# Volant5.net
KiCad netlist of a schematic drawn in Altium Designer
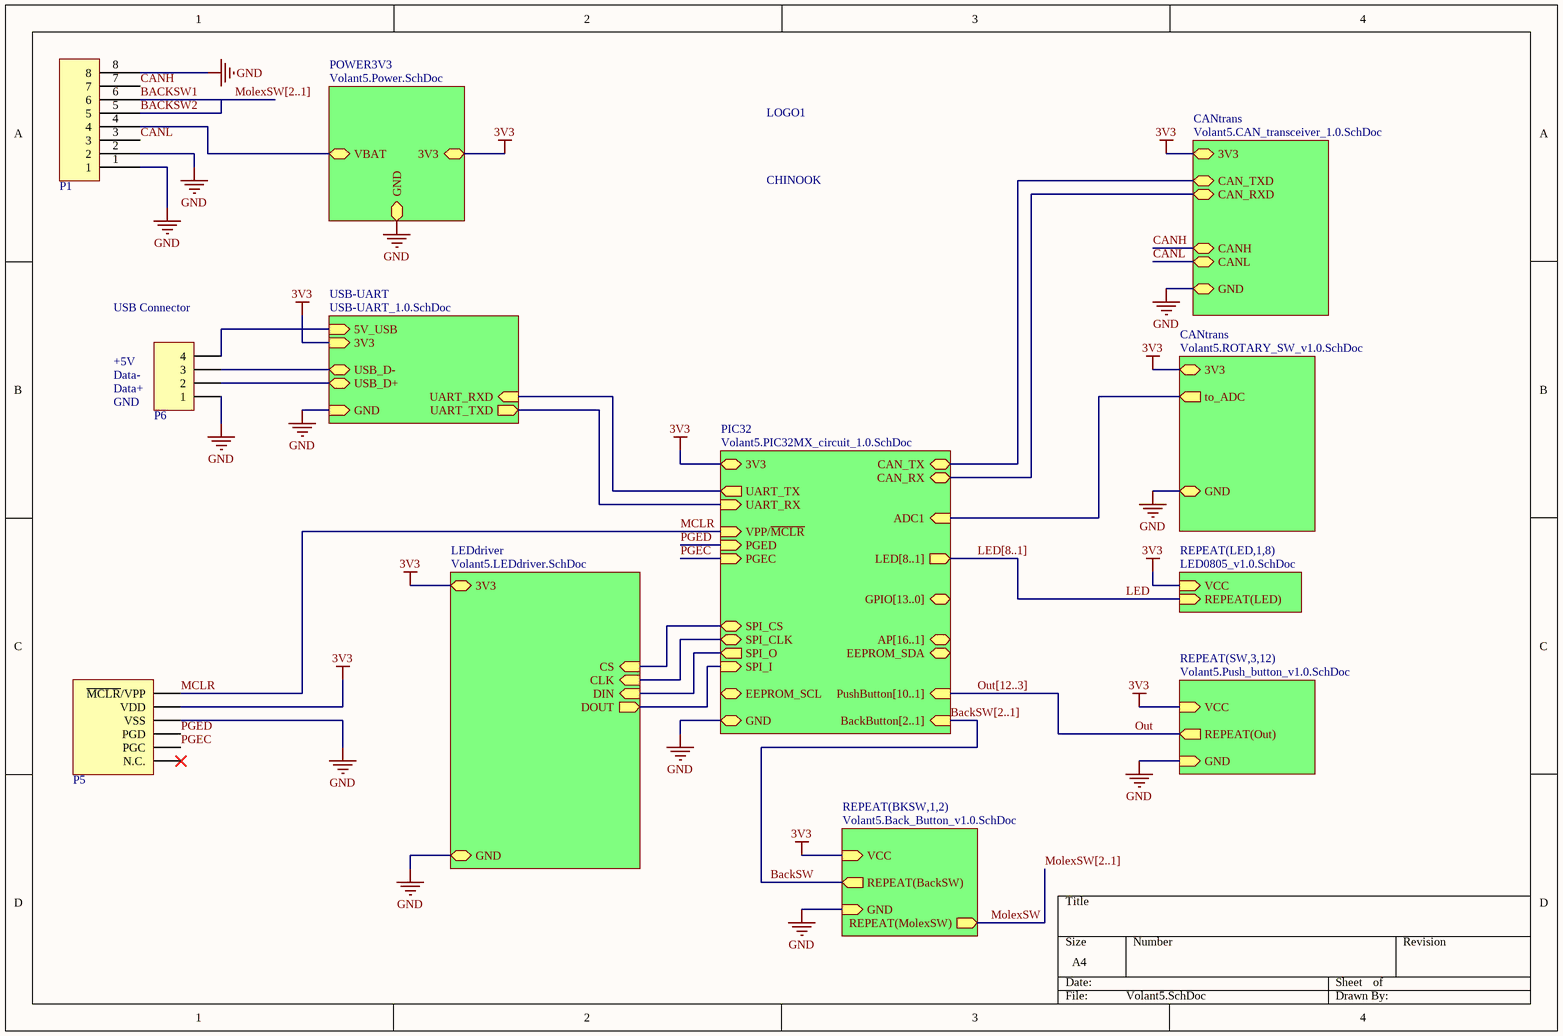
[diagram p0: Volant5.SchDoc]

(export (version "E")
  (design (tool "Eeschema 10.0.6"))
  (components
    (comp (ref "LOGO1")
      (value "CHINOOK")
      (footprint "LOGO-CHINOOK")
      (libsource (lib "CHINOOK_LIBRARY") (part "LOGO - FOOTPRINT"))
    )
    (comp (ref "P1")
      (value "CON - MOLEX 8POS")
      (footprint "CON-MOLEX Mini Jr 8pin - RA")
      (description "Mini-Fit Jr 8pin")
      (fields (field (name "MANUFACTURER") "MOLEX"))
      (libsource (lib "CHINOOK_LIBRARY") (part "CON - MOLEX 8POS"))
    )
    (comp (ref "P5")
      (value "CON - HEADER PROG")
      (footprint "CON-PROG-PIC")
      (description "MICROCHIP CONNECTOR")
      (libsource (lib "CHINOOK-FOOTPRINT") (part "CON - PROG HEADER 6"))
    )
    (comp (ref "P6")
      (value "CON - HEADER 1X4")
      (footprint "CON-HEADER-1X4")
      (description "100mil header 1 row 4pins")
      (libsource (lib "CHINOOK_LIBRARY") (part "CON - HEADER 1X4"))
    )
  )
  (nets
    (net (code "23") (name "/5V_USB") (class "Default")
      (node (ref "P6") (pin "4") (pinfunction "4_4") (pintype "passive"))
    )
    (net (code "25") (name "/BACKSW1") (class "Default")
      (node (ref "P1") (pin "6") (pinfunction "6_6") (pintype "passive"))
    )
    (net (code "26") (name "/BACKSW2") (class "Default")
      (node (ref "P1") (pin "5") (pinfunction "5_5") (pintype "passive"))
    )
    (net (code "29") (name "/CANH") (class "Default")
      (node (ref "P1") (pin "7") (pinfunction "7_7") (pintype "passive"))
    )
    (net (code "30") (name "/CANL") (class "Default")
      (node (ref "P1") (pin "3") (pinfunction "3_3") (pintype "passive"))
    )
    (net (code "41") (name "/MCLR") (class "Default")
      (node (ref "P5") (pin "1") (pinfunction "~{MCLR}/VPP_1") (pintype "passive"))
    )
    (net (code "46") (name "/PGEC") (class "Default")
      (node (ref "P5") (pin "5") (pinfunction "PGC_5") (pintype "passive"))
    )
    (net (code "47") (name "/PGED") (class "Default")
      (node (ref "P5") (pin "4") (pinfunction "PGD_4") (pintype "passive"))
    )
    (net (code "51") (name "/USB_D+") (class "Default")
      (node (ref "P6") (pin "2") (pinfunction "2_2") (pintype "passive"))
    )
    (net (code "52") (name "/USB_D-") (class "Default")
      (node (ref "P6") (pin "3") (pinfunction "3_3") (pintype "passive"))
    )
    (net (code "53") (name "/VBAT") (class "Default")
      (node (ref "P1") (pin "4") (pinfunction "4_4") (pintype "passive"))
    )
    (net (code "55") (name "3V3") (class "Default")
      (node (ref "P5") (pin "2") (pinfunction "VDD_2") (pintype "passive"))
    )
    (net (code "56") (name "GND") (class "Default")
      (node (ref "P1") (pin "1") (pinfunction "1_1") (pintype "passive"))
      (node (ref "P1") (pin "2") (pinfunction "2_2") (pintype "passive"))
      (node (ref "P1") (pin "8") (pinfunction "8_8") (pintype "passive"))
      (node (ref "P5") (pin "3") (pinfunction "VSS_3") (pintype "passive"))
      (node (ref "P6") (pin "1") (pinfunction "1_1") (pintype "passive"))
    )
    (net (code "57") (name "unconnected-(P5-N.C.-Pad6)") (class "Default")
      (node (ref "P5") (pin "6") (pinfunction "N.C._6") (pintype "passive+no_connect"))
    )
  )
)
